# PIEFoundry_32-channel_EIB.net
KiCad netlist of a schematic drawn in EAGLE
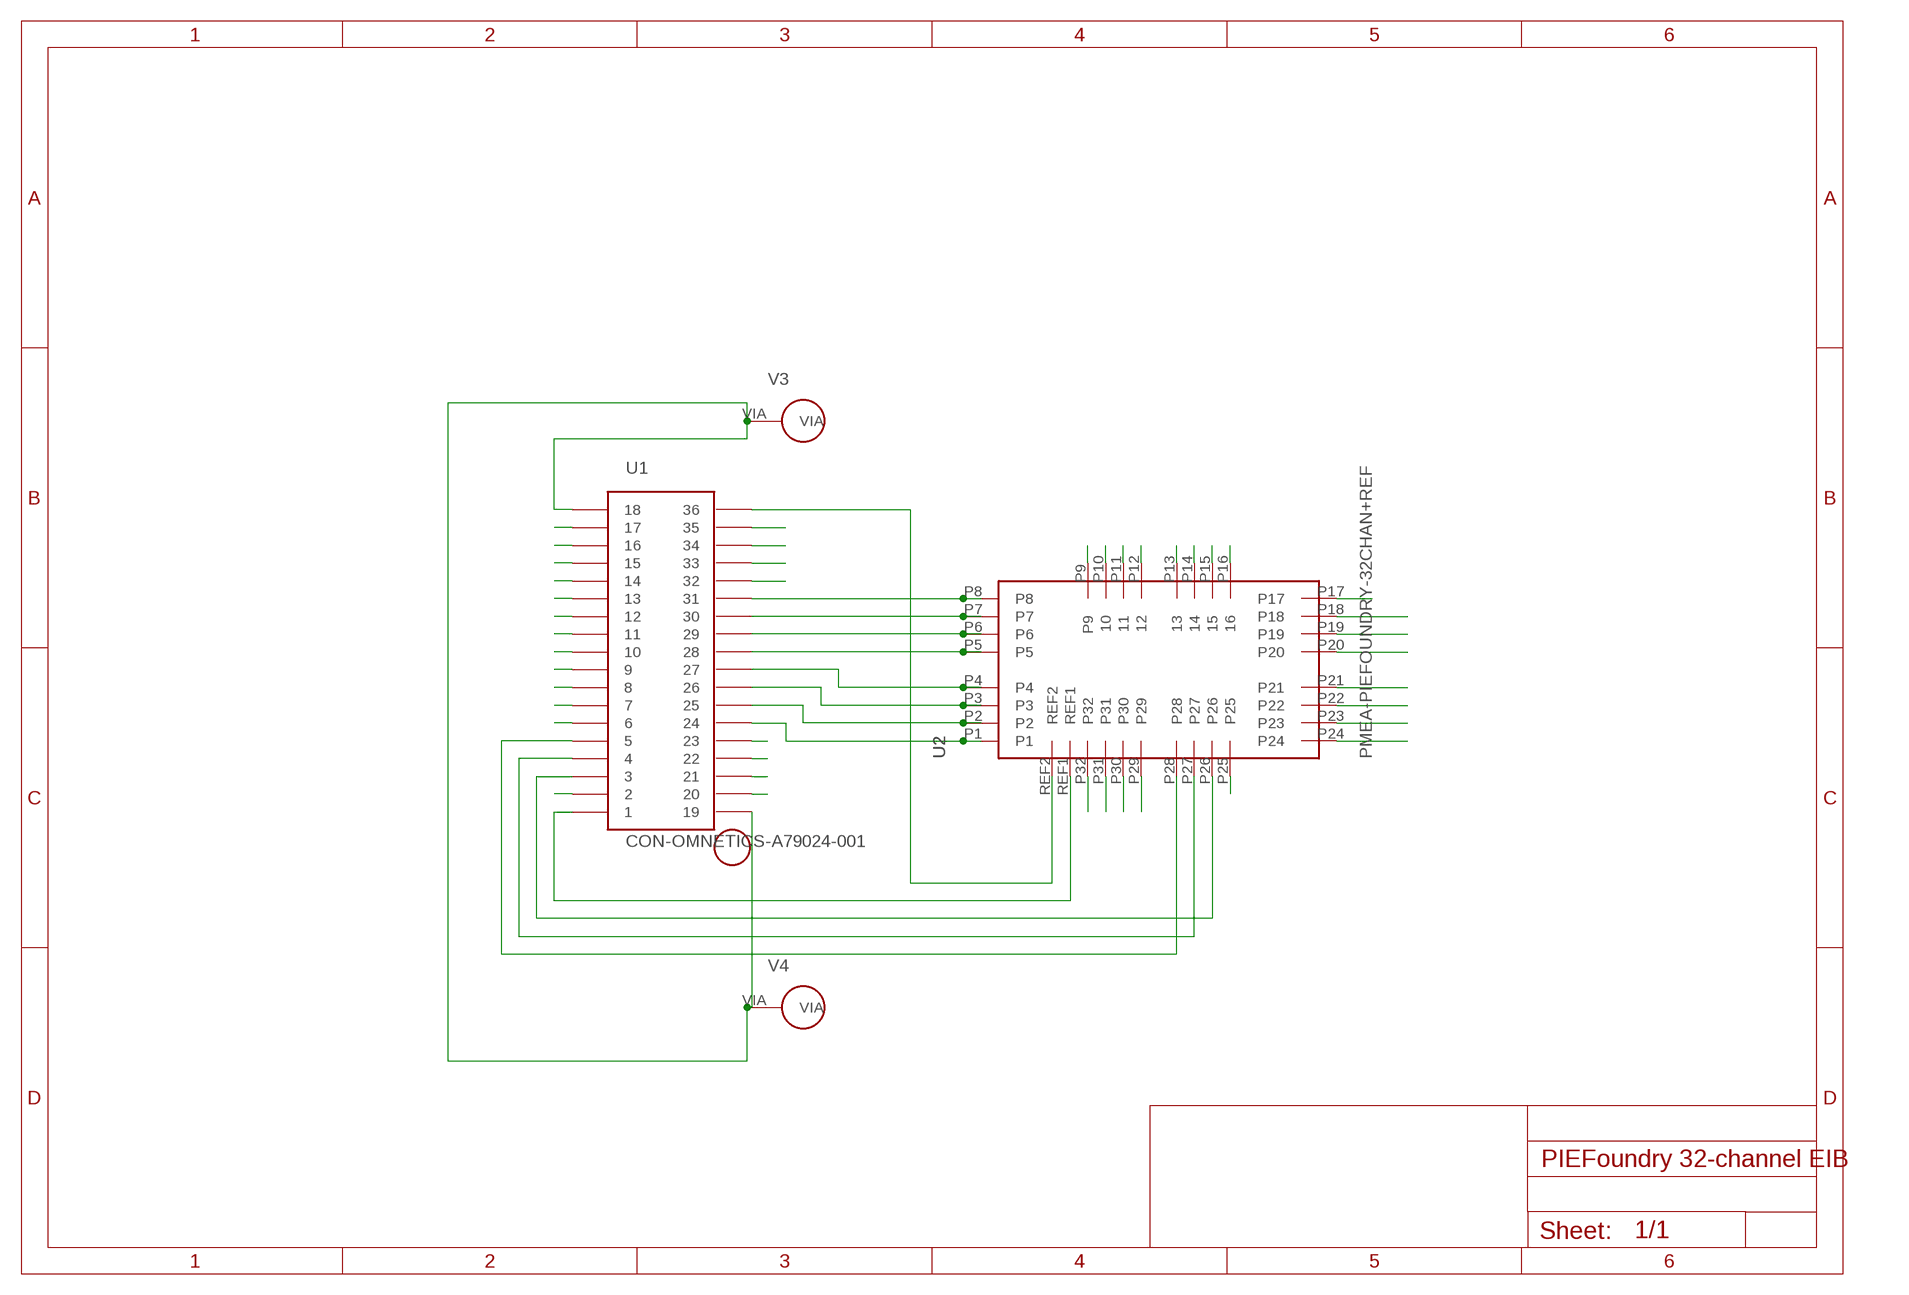
[diagram p0: schematic, sheet 1]

(export (version "E")
  (design (tool "Eeschema 10.0.6"))
  (components
    (comp (ref "U1")
      (value "CON-OMNETICS-A79024-001")
      (footprint "eagle-import:CON-OMNETICS-A79024-001")
      (libsource (lib "eagle-import") (part "CON-OMNETICS-A79024-001"))
    )
    (comp (ref "U2")
      (value "PMEA-PIEFOUNDRY-32CHAN+REF")
      (footprint "eagle-import:PMEA-PIEFOUNDRY-32CHAN+REF")
      (libsource (lib "eagle-import") (part "PMEA-PIEFOUNDRY-32CHAN+REF"))
    )
    (comp (ref "V3")
      (value "SOLDER_VIA_500_UM")
      (footprint "eagle-import:SOLDER_VIA_500_UM")
      (libsource (lib "eagle-import") (part "SOLDER_VIA_500_UM"))
    )
    (comp (ref "V4")
      (value "SOLDER_VIA_500_UM")
      (footprint "eagle-import:SOLDER_VIA_500_UM")
      (libsource (lib "eagle-import") (part "SOLDER_VIA_500_UM"))
    )
  )
  (nets
    (net (code "1") (name "/P9") (class "Default")
      (node (ref "U1") (pin "20") (pinfunction "20_20") (pintype "bidirectional"))
      (node (ref "U2") (pin "P9") (pinfunction "P9_P9") (pintype "bidirectional"))
    )
    (net (code "2") (name "/P10") (class "Default")
      (node (ref "U1") (pin "21") (pinfunction "21_21") (pintype "bidirectional"))
      (node (ref "U2") (pin "P10") (pinfunction "10_P10") (pintype "bidirectional"))
    )
    (net (code "3") (name "/P11") (class "Default")
      (node (ref "U1") (pin "22") (pinfunction "22_22") (pintype "bidirectional"))
      (node (ref "U2") (pin "P11") (pinfunction "11_P11") (pintype "bidirectional"))
    )
    (net (code "4") (name "/P12") (class "Default")
      (node (ref "U1") (pin "23") (pinfunction "23_23") (pintype "bidirectional"))
      (node (ref "U2") (pin "P12") (pinfunction "12_P12") (pintype "bidirectional"))
    )
    (net (code "5") (name "/P13") (class "Default")
      (node (ref "U1") (pin "32") (pinfunction "32_32") (pintype "bidirectional"))
      (node (ref "U2") (pin "P13") (pinfunction "13_P13") (pintype "bidirectional"))
    )
    (net (code "6") (name "/P14") (class "Default")
      (node (ref "U1") (pin "33") (pinfunction "33_33") (pintype "bidirectional"))
      (node (ref "U2") (pin "P14") (pinfunction "14_P14") (pintype "bidirectional"))
    )
    (net (code "7") (name "/P15") (class "Default")
      (node (ref "U1") (pin "34") (pinfunction "34_34") (pintype "bidirectional"))
      (node (ref "U2") (pin "P15") (pinfunction "15_P15") (pintype "bidirectional"))
    )
    (net (code "8") (name "/P16") (class "Default")
      (node (ref "U1") (pin "35") (pinfunction "35_35") (pintype "bidirectional"))
      (node (ref "U2") (pin "P16") (pinfunction "16_P16") (pintype "bidirectional"))
    )
    (net (code "9") (name "/P17") (class "Default")
      (node (ref "U1") (pin "6") (pinfunction "6_6") (pintype "bidirectional"))
      (node (ref "U2") (pin "P17") (pinfunction "P17_P17") (pintype "bidirectional"))
    )
    (net (code "10") (name "/P18") (class "Default")
      (node (ref "U1") (pin "7") (pinfunction "7_7") (pintype "bidirectional"))
      (node (ref "U2") (pin "P18") (pinfunction "P18_P18") (pintype "bidirectional"))
    )
    (net (code "11") (name "/P19") (class "Default")
      (node (ref "U1") (pin "8") (pinfunction "8_8") (pintype "bidirectional"))
      (node (ref "U2") (pin "P19") (pinfunction "P19_P19") (pintype "bidirectional"))
    )
    (net (code "12") (name "/P20") (class "Default")
      (node (ref "U1") (pin "9") (pinfunction "9_9") (pintype "bidirectional"))
      (node (ref "U2") (pin "P20") (pinfunction "P20_P20") (pintype "bidirectional"))
    )
    (net (code "13") (name "/P21") (class "Default")
      (node (ref "U1") (pin "10") (pinfunction "10_10") (pintype "bidirectional"))
      (node (ref "U2") (pin "P21") (pinfunction "P21_P21") (pintype "bidirectional"))
    )
    (net (code "14") (name "/P22") (class "Default")
      (node (ref "U1") (pin "11") (pinfunction "11_11") (pintype "bidirectional"))
      (node (ref "U2") (pin "P22") (pinfunction "P22_P22") (pintype "bidirectional"))
    )
    (net (code "15") (name "/P23") (class "Default")
      (node (ref "U1") (pin "12") (pinfunction "12_12") (pintype "bidirectional"))
      (node (ref "U2") (pin "P23") (pinfunction "P23_P23") (pintype "bidirectional"))
    )
    (net (code "16") (name "/P24") (class "Default")
      (node (ref "U1") (pin "13") (pinfunction "13_13") (pintype "bidirectional"))
      (node (ref "U2") (pin "P24") (pinfunction "P24_P24") (pintype "bidirectional"))
    )
    (net (code "17") (name "/P25") (class "Default")
      (node (ref "U1") (pin "2") (pinfunction "2_2") (pintype "bidirectional"))
      (node (ref "U2") (pin "P25") (pinfunction "P25_P25") (pintype "bidirectional"))
    )
    (net (code "18") (name "/P29") (class "Default")
      (node (ref "U1") (pin "14") (pinfunction "14_14") (pintype "bidirectional"))
      (node (ref "U2") (pin "P29") (pinfunction "P29_P29") (pintype "bidirectional"))
    )
    (net (code "19") (name "/P30") (class "Default")
      (node (ref "U1") (pin "15") (pinfunction "15_15") (pintype "bidirectional"))
      (node (ref "U2") (pin "P30") (pinfunction "P30_P30") (pintype "bidirectional"))
    )
    (net (code "20") (name "/P31") (class "Default")
      (node (ref "U1") (pin "16") (pinfunction "16_16") (pintype "bidirectional"))
      (node (ref "U2") (pin "P31") (pinfunction "P31_P31") (pintype "bidirectional"))
    )
    (net (code "21") (name "/P32") (class "Default")
      (node (ref "U1") (pin "17") (pinfunction "17_17") (pintype "bidirectional"))
      (node (ref "U2") (pin "P32") (pinfunction "P32_P32") (pintype "bidirectional"))
    )
    (net (code "22") (name "Net-(U1-Pad1)") (class "Default")
      (node (ref "U1") (pin "1") (pinfunction "1_1") (pintype "bidirectional"))
      (node (ref "U2") (pin "REF1") (pinfunction "REF1_REF1") (pintype "bidirectional"))
    )
    (net (code "23") (name "Net-(U1-Pad3)") (class "Default")
      (node (ref "U1") (pin "3") (pinfunction "3_3") (pintype "bidirectional"))
      (node (ref "U2") (pin "P26") (pinfunction "P26_P26") (pintype "bidirectional"))
    )
    (net (code "24") (name "Net-(U1-Pad4)") (class "Default")
      (node (ref "U1") (pin "4") (pinfunction "4_4") (pintype "bidirectional"))
      (node (ref "U2") (pin "P27") (pinfunction "P27_P27") (pintype "bidirectional"))
    )
    (net (code "25") (name "Net-(U1-Pad5)") (class "Default")
      (node (ref "U1") (pin "5") (pinfunction "5_5") (pintype "bidirectional"))
      (node (ref "U2") (pin "P28") (pinfunction "P28_P28") (pintype "bidirectional"))
    )
    (net (code "26") (name "Net-(U1-Pad18)") (class "Default")
      (node (ref "U1") (pin "18") (pinfunction "18_18") (pintype "bidirectional"))
      (node (ref "U1") (pin "19") (pinfunction "19_19") (pintype "bidirectional"))
      (node (ref "V3") (pin "VIA") (pinfunction "VIA_VIA") (pintype "bidirectional"))
      (node (ref "V4") (pin "VIA") (pinfunction "VIA_VIA") (pintype "bidirectional"))
    )
    (net (code "27") (name "Net-(U1-Pad24)") (class "Default")
      (node (ref "U1") (pin "24") (pinfunction "24_24") (pintype "bidirectional"))
      (node (ref "U2") (pin "P1") (pinfunction "P1_P1") (pintype "bidirectional"))
    )
    (net (code "28") (name "Net-(U1-Pad25)") (class "Default")
      (node (ref "U1") (pin "25") (pinfunction "25_25") (pintype "bidirectional"))
      (node (ref "U2") (pin "P2") (pinfunction "P2_P2") (pintype "bidirectional"))
    )
    (net (code "29") (name "Net-(U1-Pad26)") (class "Default")
      (node (ref "U1") (pin "26") (pinfunction "26_26") (pintype "bidirectional"))
      (node (ref "U2") (pin "P3") (pinfunction "P3_P3") (pintype "bidirectional"))
    )
    (net (code "30") (name "Net-(U1-Pad27)") (class "Default")
      (node (ref "U1") (pin "27") (pinfunction "27_27") (pintype "bidirectional"))
      (node (ref "U2") (pin "P4") (pinfunction "P4_P4") (pintype "bidirectional"))
    )
    (net (code "31") (name "Net-(U1-Pad28)") (class "Default")
      (node (ref "U1") (pin "28") (pinfunction "28_28") (pintype "bidirectional"))
      (node (ref "U2") (pin "P5") (pinfunction "P5_P5") (pintype "bidirectional"))
    )
    (net (code "32") (name "Net-(U1-Pad29)") (class "Default")
      (node (ref "U1") (pin "29") (pinfunction "29_29") (pintype "bidirectional"))
      (node (ref "U2") (pin "P6") (pinfunction "P6_P6") (pintype "bidirectional"))
    )
    (net (code "33") (name "Net-(U1-Pad30)") (class "Default")
      (node (ref "U1") (pin "30") (pinfunction "30_30") (pintype "bidirectional"))
      (node (ref "U2") (pin "P7") (pinfunction "P7_P7") (pintype "bidirectional"))
    )
    (net (code "34") (name "Net-(U1-Pad31)") (class "Default")
      (node (ref "U1") (pin "31") (pinfunction "31_31") (pintype "bidirectional"))
      (node (ref "U2") (pin "P8") (pinfunction "P8_P8") (pintype "bidirectional"))
    )
    (net (code "35") (name "Net-(U1-Pad36)") (class "Default")
      (node (ref "U1") (pin "36") (pinfunction "36_36") (pintype "bidirectional"))
      (node (ref "U2") (pin "REF2") (pinfunction "REF2_REF2") (pintype "bidirectional"))
    )
  )
)
